# MohamedAazir_WirelessEMG__version_1_0_PC.net
KiCad netlist of a schematic drawn in Altium Designer
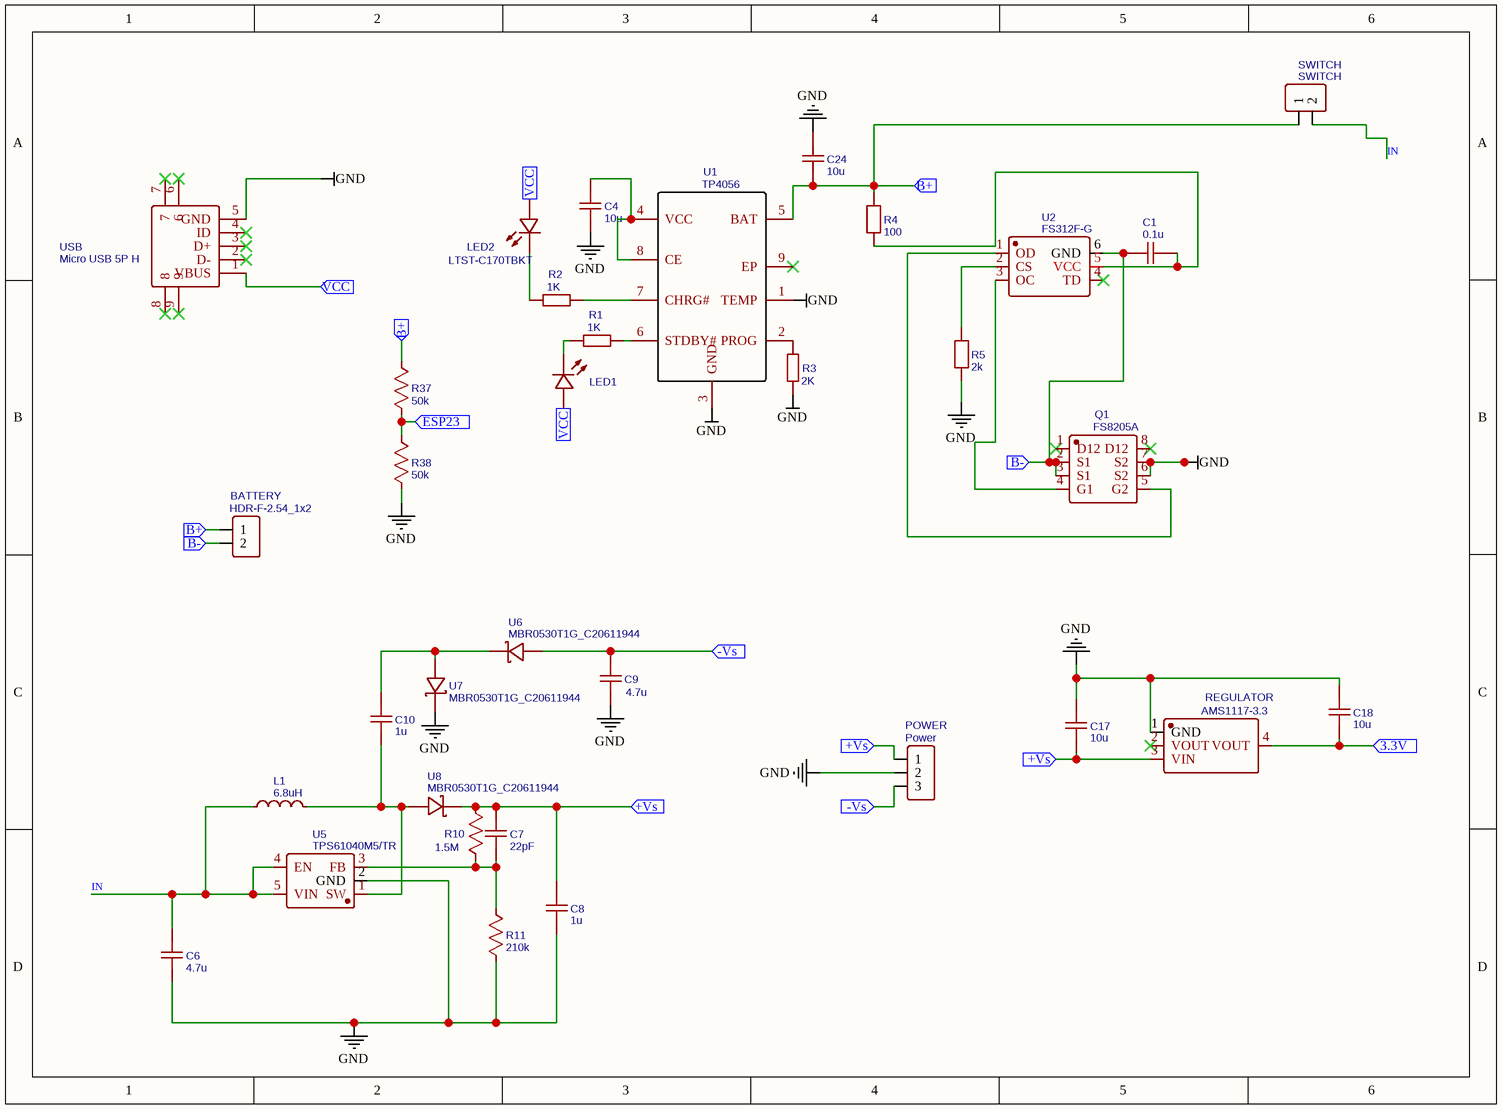
[diagram p0: MohamedAazir_WirelessEMG__version_1.0_PCB__Power.schdoc]

(export (version "E")
  (design (tool "Eeschema 10.0.6"))
  (components
    (comp (ref "BATTERY")
      (value "HDR-F-2.54_1x2")
      (fields
        (field (name "MANUFACTURER") "HC(虹成电子)")
        (field (name "MANUFACTURER PART") "HC-PM254-8.5H-1x2PZ")
        (field (name "CONTRIBUTOR") "LCEDA_Lib")
      )
      (libsource (lib "altium-import") (part "root_0_HDR-F-2.54_1x2_"))
    )
    (comp (ref "C1")
      (value "0.1u")
      (fields
        (field (name "MANUFACTURER PART") "RF18N0R1B500CT")
        (field (name "MANUFACTURER") "Walsin(华新科)")
        (field (name "CONTRIBUTOR") "LCEDA_Lib")
      )
      (libsource (lib "altium-import") (part "root_0_0.1u_"))
    )
    (comp (ref "C4")
      (value "10u")
      (fields
        (field (name "MANUFACTURER PART") "CA45A-P-10V-10uF-K")
        (field (name "MANUFACTURER") "CEC(振华新云)")
        (field (name "CONTRIBUTOR") "LCEDA_Lib")
      )
      (libsource (lib "altium-import") (part "root_3_10u_"))
    )
    (comp (ref "C6")
      (value "4.7u")
      (fields
        (field (name "MANUFACTURER PART") "CA45B-A-25V-4.7UF-K")
        (field (name "MANUFACTURER") "CEC(振华新云)")
        (field (name "CONTRIBUTOR") "LCEDA_Lib")
      )
      (libsource (lib "altium-import") (part "root_1_4.7u_"))
    )
    (comp (ref "C7")
      (value "22pF")
      (fields
        (field (name "MANUFACTURER PART") "0805N220J500CT-C")
        (field (name "MANUFACTURER") "Walsin(华新科)")
        (field (name "CONTRIBUTOR") "LCEDA_Lib")
      )
      (libsource (lib "altium-import") (part "root_1_22pF_"))
    )
    (comp (ref "C8")
      (value "1u")
      (fields
        (field (name "MANUFACTURER PART") "T491B105M035AT")
        (field (name "MANUFACTURER") "KEMET(基美)")
        (field (name "CONTRIBUTOR") "LCEDA_Lib")
      )
      (libsource (lib "altium-import") (part "root_1_1u_"))
    )
    (comp (ref "C9")
      (value "4.7u")
      (fields
        (field (name "MANUFACTURER PART") "CA45B-A-25V-4.7UF-K")
        (field (name "MANUFACTURER") "CEC(振华新云)")
        (field (name "CONTRIBUTOR") "LCEDA_Lib")
      )
      (libsource (lib "altium-import") (part "root_1_4.7u_"))
    )
    (comp (ref "C10")
      (value "1u")
      (fields
        (field (name "MANUFACTURER PART") "T491B105M035AT")
        (field (name "MANUFACTURER") "KEMET(基美)")
        (field (name "CONTRIBUTOR") "LCEDA_Lib")
      )
      (libsource (lib "altium-import") (part "root_1_1u_"))
    )
    (comp (ref "C17")
      (value "10u")
      (fields
        (field (name "MANUFACTURER PART") "CGA3E1X7T0G106MT0YHN")
        (field (name "MANUFACTURER") "TDK")
        (field (name "CONTRIBUTOR") "LCEDA_Lib")
      )
      (libsource (lib "altium-import") (part "root_1_10u_"))
    )
    (comp (ref "C18")
      (value "10u")
      (fields
        (field (name "MANUFACTURER PART") "CGA3E1X7T0G106MT0YHN")
        (field (name "MANUFACTURER") "TDK")
        (field (name "CONTRIBUTOR") "LCEDA_Lib")
      )
      (libsource (lib "altium-import") (part "root_1_10u_"))
    )
    (comp (ref "C24")
      (value "10u")
      (fields (field (name "CONTRIBUTOR") "LCEDA_Lib"))
      (libsource (lib "altium-import") (part "root_1_10u_"))
    )
    (comp (ref "L1")
      (value "6.8uH")
      (fields
        (field (name "MANUFACTURER PART") "BWVF00303015220M00")
        (field (name "MANUFACTURER") "chilisin(奇力新)")
        (field (name "CONTRIBUTOR") "LCEDA_Lib")
      )
      (libsource (lib "altium-import") (part "root_0_6.8uH_"))
    )
    (comp (ref "LED1")
      (value "0805G (Green)")
      (fields (field (name "MANUFACTURER") "KENTO"))
      (libsource (lib "altium-import") (part "root_3_0805G (Green)_"))
    )
    (comp (ref "LED2")
      (value "LTST-C170TBKT")
      (fields (field (name "MANUFACTURER PART") "LED05-红灯") (field (name "CONTRIBUTOR") "LCSC"))
      (libsource (lib "altium-import") (part "root_1_LTST-C170TBKT_"))
    )
    (comp (ref "POWER")
      (value "Power")
      (fields (field (name "MANUFACTURER") "BOOMELE(博穆精密)") (field (name "MANUFACTURER PART") "2.54-1*3P母"))
      (libsource (lib "altium-import") (part "root_0_Power_"))
    )
    (comp (ref "Q1")
      (value "FS8205A")
      (fields (field (name "MANUFACTURER") "FORTUNE"))
      (libsource (lib "altium-import") (part "root_0_FS8205A_"))
    )
    (comp (ref "R1")
      (value "1K")
      (fields
        (field (name "MANUFACTURER") "ResistorToday")
        (field (name "MANUFACTURER PART") "AECR0603F1K00K9")
        (field (name "CONTRIBUTOR") "LCSC")
      )
      (libsource (lib "altium-import") (part "root_0_1K_"))
    )
    (comp (ref "R2")
      (value "1K")
      (fields
        (field (name "MANUFACTURER") "ResistorToday")
        (field (name "MANUFACTURER PART") "AECR0603F1K00K9")
        (field (name "CONTRIBUTOR") "LCSC")
      )
      (libsource (lib "altium-import") (part "root_0_1K_"))
    )
    (comp (ref "R3")
      (value "2K")
      (fields
        (field (name "MANUFACTURER") "Tyohm")
        (field (name "MANUFACTURER PART") "RMC06031.2K5%N")
        (field (name "CONTRIBUTOR") "LCSC")
      )
      (libsource (lib "altium-import") (part "root_1_2K_"))
    )
    (comp (ref "R4")
      (value "100")
      (fields
        (field (name "MANUFACTURER PART") "RC0R5DB100RJET")
        (field (name "MANUFACTURER") "Ohmite")
        (field (name "CONTRIBUTOR") "LCEDA_Lib")
      )
      (libsource (lib "altium-import") (part "root_3_100_"))
    )
    (comp (ref "R5")
      (value "2k")
      (fields
        (field (name "MANUFACTURER PART") "CSR0204FTDV2001")
        (field (name "MANUFACTURER") "Viking(光颉)")
        (field (name "CONTRIBUTOR") "LCEDA_Lib")
      )
      (libsource (lib "altium-import") (part "root_1_2k_"))
    )
    (comp (ref "R10")
      (value "1.5M")
      (fields
        (field (name "MANUFACTURER PART") "WR02X155JAL")
        (field (name "MANUFACTURER") "Walsin(华新科)")
        (field (name "CONTRIBUTOR") "LCEDA_Lib")
      )
      (libsource (lib "altium-import") (part "root_1_1.5M_"))
    )
    (comp (ref "R11")
      (value "210k")
      (fields
        (field (name "MANUFACTURER PART") "FRC0805F2103TS")
        (field (name "MANUFACTURER") "FOJAN(富捷)")
        (field (name "CONTRIBUTOR") "LCEDA_Lib")
      )
      (libsource (lib "altium-import") (part "root_1_210k_"))
    )
    (comp (ref "R37")
      (value "50k")
      (fields
        (field (name "MANUFACTURER PART") "RT0603BRD0750KL")
        (field (name "MANUFACTURER") "YAGEO(国巨)")
        (field (name "CONTRIBUTOR") "LCEDA_Lib")
      )
      (libsource (lib "altium-import") (part "root_1_50k_"))
    )
    (comp (ref "R38")
      (value "50k")
      (fields
        (field (name "MANUFACTURER PART") "RT0603BRD0750KL")
        (field (name "MANUFACTURER") "YAGEO(国巨)")
        (field (name "CONTRIBUTOR") "LCEDA_Lib")
      )
      (libsource (lib "altium-import") (part "root_1_50k_"))
    )
    (comp (ref "REGULATOR")
      (value "AMS1117-3.3")
      (fields (field (name "MANUFACTURER") "AMS"))
      (libsource (lib "altium-import") (part "root_0_AMS1117-3.3_"))
    )
    (comp (ref "SWITCH")
      (value "SWITCH")
      (fields
        (field (name "MANUFACTURER") "HC(虹成电子)")
        (field (name "MANUFACTURER PART") "HC-PM254-8.5H-1x2PZ")
        (field (name "CONTRIBUTOR") "LCEDA_Lib")
      )
      (libsource (lib "altium-import") (part "root_1_SWITCH_"))
    )
    (comp (ref "U1")
      (value "TP4056")
      (fields (field (name "MANUFACTURER") "TOPPOWER") (field (name "CONTRIBUTOR") "Guest"))
      (libsource (lib "altium-import") (part "root_0_TP4056_"))
    )
    (comp (ref "U2")
      (value "FS312F-G")
      (fields (field (name "MANUFACTURER") "FORTUNE(富晶)"))
      (libsource (lib "altium-import") (part "root_0_FS312F-G_"))
    )
    (comp (ref "U5")
      (value "TPS61040M5/TR")
      (fields (field (name "MANUFACTURER") "HGSEMI(华冠)") (field (name "CONTRIBUTOR") "lcsc"))
      (libsource (lib "altium-import") (part "root_2_TPS61040M5/TR_"))
    )
    (comp (ref "U6")
      (value "MBR0530T1G_C20611944")
      (fields
        (field (name "MANUFACTURER") "HXY MOSFET(华轩阳电子)")
        (field (name "MANUFACTURER PART") "MBR0530T1G")
        (field (name "CONTRIBUTOR") "lcsc")
      )
      (libsource (lib "altium-import") (part "root_0_MBR0530T1G_C20611944_"))
    )
    (comp (ref "U7")
      (value "MBR0530T1G_C20611944")
      (fields
        (field (name "MANUFACTURER") "HXY MOSFET(华轩阳电子)")
        (field (name "MANUFACTURER PART") "MBR0530T1G")
        (field (name "CONTRIBUTOR") "lcsc")
      )
      (libsource (lib "altium-import") (part "root_1_MBR0530T1G_C20611944_"))
    )
    (comp (ref "U8")
      (value "MBR0530T1G_C20611944")
      (fields
        (field (name "MANUFACTURER") "HXY MOSFET(华轩阳电子)")
        (field (name "MANUFACTURER PART") "MBR0530T1G")
        (field (name "CONTRIBUTOR") "lcsc")
      )
      (libsource (lib "altium-import") (part "root_2_MBR0530T1G_C20611944_"))
    )
    (comp (ref "USB")
      (value "Micro USB 5P H")
      (fields
        (field (name "MANUFACTURER") "精拓金")
        (field (name "MANUFACTURER PART") "920-E52A2021S10101")
        (field (name "CONTRIBUTOR") "LCSC")
      )
      (libsource (lib "altium-import") (part "root_2_Micro USB 5P H_"))
    )
  )
  (nets
    (net (code "1") (name "/+Vs") (class "Default")
      (node (ref "C17") (pin "1") (pinfunction "1_1") (pintype "passive"))
      (node (ref "C7") (pin "2") (pinfunction "2_2") (pintype "passive"))
      (node (ref "C8") (pin "2") (pinfunction "2_2") (pintype "passive"))
      (node (ref "POWER") (pin "1") (pinfunction "1_1") (pintype "passive"))
      (node (ref "R10") (pin "2") (pinfunction "2_2") (pintype "passive"))
      (node (ref "REGULATOR") (pin "3") (pinfunction "VIN_3") (pintype "passive"))
      (node (ref "U8") (pin "1") (pinfunction "K_1") (pintype "passive"))
    )
    (net (code "2") (name "/-Vs") (class "Default")
      (node (ref "C9") (pin "2") (pinfunction "2_2") (pintype "passive"))
      (node (ref "POWER") (pin "3") (pinfunction "3_3") (pintype "passive"))
      (node (ref "U6") (pin "2") (pinfunction "A_2") (pintype "passive"))
    )
    (net (code "3") (name "/3.3V") (class "Default")
      (node (ref "C18") (pin "1") (pinfunction "1_1") (pintype "passive"))
      (node (ref "REGULATOR") (pin "4") (pinfunction "VOUT_4") (pintype "passive"))
    )
    (net (code "4") (name "/B+") (class "Default")
      (node (ref "BATTERY") (pin "1") (pinfunction "1_1") (pintype "passive"))
      (node (ref "C24") (pin "1") (pinfunction "1_1") (pintype "passive"))
      (node (ref "R37") (pin "2") (pinfunction "2_2") (pintype "passive"))
      (node (ref "R4") (pin "1") (pinfunction "1_1") (pintype "passive"))
      (node (ref "SWITCH") (pin "1") (pinfunction "1_1") (pintype "passive"))
      (node (ref "U1") (pin "5") (pinfunction "BAT_5") (pintype "passive"))
    )
    (net (code "5") (name "/B-") (class "Default")
      (node (ref "BATTERY") (pin "2") (pinfunction "2_2") (pintype "passive"))
      (node (ref "C1") (pin "1") (pinfunction "1_1") (pintype "passive"))
      (node (ref "Q1") (pin "2") (pinfunction "S1_2") (pintype "passive"))
      (node (ref "Q1") (pin "3") (pinfunction "S1_3") (pintype "passive"))
      (node (ref "U2") (pin "6") (pinfunction "GND_6") (pintype "passive"))
    )
    (net (code "6") (name "/ESP23") (class "Default")
      (node (ref "R37") (pin "1") (pinfunction "1_1") (pintype "passive"))
      (node (ref "R38") (pin "2") (pinfunction "2_2") (pintype "passive"))
    )
    (net (code "7") (name "/IN") (class "Default")
      (node (ref "C6") (pin "2") (pinfunction "2_2") (pintype "passive"))
      (node (ref "L1") (pin "1") (pinfunction "1_1") (pintype "passive"))
      (node (ref "SWITCH") (pin "2") (pinfunction "2_2") (pintype "passive"))
      (node (ref "U5") (pin "4") (pinfunction "EN_4") (pintype "passive"))
      (node (ref "U5") (pin "5") (pinfunction "VIN_5") (pintype "passive"))
    )
    (net (code "8") (name "/VCC") (class "Default")
      (node (ref "LED1") (pin "2") (pinfunction "A_2") (pintype "passive"))
      (node (ref "LED2") (pin "2") (pinfunction "A_2") (pintype "passive"))
      (node (ref "USB") (pin "1") (pinfunction "VBUS_1") (pintype "passive"))
    )
    (net (code "9") (name "GND") (class "Default")
      (node (ref "C17") (pin "2") (pinfunction "2_2") (pintype "passive"))
      (node (ref "C18") (pin "2") (pinfunction "2_2") (pintype "passive"))
      (node (ref "C24") (pin "2") (pinfunction "2_2") (pintype "passive"))
      (node (ref "C4") (pin "2") (pinfunction "2_2") (pintype "passive"))
      (node (ref "C6") (pin "1") (pinfunction "1_1") (pintype "passive"))
      (node (ref "C8") (pin "1") (pinfunction "1_1") (pintype "passive"))
      (node (ref "C9") (pin "1") (pinfunction "1_1") (pintype "passive"))
      (node (ref "POWER") (pin "2") (pinfunction "2_2") (pintype "passive"))
      (node (ref "Q1") (pin "6") (pinfunction "S2_6") (pintype "passive"))
      (node (ref "Q1") (pin "7") (pinfunction "S2_7") (pintype "passive"))
      (node (ref "R11") (pin "1") (pinfunction "1_1") (pintype "passive"))
      (node (ref "R3") (pin "1") (pinfunction "1_1") (pintype "passive"))
      (node (ref "R38") (pin "1") (pinfunction "1_1") (pintype "passive"))
      (node (ref "R5") (pin "1") (pinfunction "1_1") (pintype "passive"))
      (node (ref "REGULATOR") (pin "1") (pinfunction "GND_1") (pintype "passive"))
      (node (ref "U1") (pin "1") (pinfunction "TEMP_1") (pintype "passive"))
      (node (ref "U1") (pin "3") (pinfunction "GND_3") (pintype "passive"))
      (node (ref "U5") (pin "2") (pinfunction "GND_2") (pintype "passive"))
      (node (ref "U7") (pin "1") (pinfunction "K_1") (pintype "passive"))
      (node (ref "USB") (pin "5") (pinfunction "GND_5") (pintype "passive"))
    )
    (net (code "10") (name "Net-(LED1-K)") (class "Default")
      (node (ref "LED1") (pin "1") (pinfunction "K_1") (pintype "passive"))
      (node (ref "R1") (pin "1") (pinfunction "1_1") (pintype "passive"))
    )
    (net (code "11") (name "Net-(LED2-K)") (class "Default")
      (node (ref "LED2") (pin "1") (pinfunction "K_1") (pintype "passive"))
      (node (ref "R2") (pin "1") (pinfunction "1_1") (pintype "passive"))
    )
    (net (code "12") (name "Net-(Q1-G1)") (class "Default")
      (node (ref "Q1") (pin "4") (pinfunction "G1_4") (pintype "passive"))
      (node (ref "U2") (pin "3") (pinfunction "OC_3") (pintype "passive"))
    )
    (net (code "13") (name "Net-(Q1-G2)") (class "Default")
      (node (ref "Q1") (pin "5") (pinfunction "G2_5") (pintype "passive"))
      (node (ref "U2") (pin "1") (pinfunction "OD_1") (pintype "passive"))
    )
    (net (code "14") (name "Net-(U1-CE)") (class "Default")
      (node (ref "C4") (pin "1") (pinfunction "1_1") (pintype "passive"))
      (node (ref "U1") (pin "4") (pinfunction "VCC_4") (pintype "passive"))
      (node (ref "U1") (pin "8") (pinfunction "CE_8") (pintype "passive"))
    )
    (net (code "15") (name "Net-(U1-CHRG#)") (class "Default")
      (node (ref "R2") (pin "2") (pinfunction "2_2") (pintype "passive"))
      (node (ref "U1") (pin "7") (pinfunction "CHRG#_7") (pintype "passive"))
    )
    (net (code "16") (name "Net-(U1-PROG)") (class "Default")
      (node (ref "R3") (pin "2") (pinfunction "2_2") (pintype "passive"))
      (node (ref "U1") (pin "2") (pinfunction "PROG_2") (pintype "passive"))
    )
    (net (code "17") (name "Net-(U1-STDBY#)") (class "Default")
      (node (ref "R1") (pin "2") (pinfunction "2_2") (pintype "passive"))
      (node (ref "U1") (pin "6") (pinfunction "STDBY#_6") (pintype "passive"))
    )
    (net (code "18") (name "Net-(U2-CS)") (class "Default")
      (node (ref "R5") (pin "2") (pinfunction "2_2") (pintype "passive"))
      (node (ref "U2") (pin "2") (pinfunction "CS_2") (pintype "passive"))
    )
    (net (code "19") (name "Net-(U2-VCC)") (class "Default")
      (node (ref "C1") (pin "2") (pinfunction "2_2") (pintype "passive"))
      (node (ref "R4") (pin "2") (pinfunction "2_2") (pintype "passive"))
      (node (ref "U2") (pin "5") (pinfunction "VCC_5") (pintype "passive"))
    )
    (net (code "20") (name "Net-(U5-FB)") (class "Default")
      (node (ref "C7") (pin "1") (pinfunction "1_1") (pintype "passive"))
      (node (ref "R10") (pin "1") (pinfunction "1_1") (pintype "passive"))
      (node (ref "R11") (pin "2") (pinfunction "2_2") (pintype "passive"))
      (node (ref "U5") (pin "3") (pinfunction "FB_3") (pintype "passive"))
    )
    (net (code "21") (name "Net-(U5-SW)") (class "Default")
      (node (ref "C10") (pin "1") (pinfunction "1_1") (pintype "passive"))
      (node (ref "L1") (pin "2") (pinfunction "2_2") (pintype "passive"))
      (node (ref "U5") (pin "1") (pinfunction "SW_1") (pintype "passive"))
      (node (ref "U8") (pin "2") (pinfunction "A_2") (pintype "passive"))
    )
    (net (code "22") (name "Net-(U6-K)") (class "Default")
      (node (ref "C10") (pin "2") (pinfunction "2_2") (pintype "passive"))
      (node (ref "U6") (pin "1") (pinfunction "K_1") (pintype "passive"))
      (node (ref "U7") (pin "2") (pinfunction "A_2") (pintype "passive"))
    )
    (net (code "23") (name "unconnected-(Q1-D12-Pad1)") (class "Default")
      (node (ref "Q1") (pin "1") (pinfunction "D12_1") (pintype "passive+no_connect"))
    )
    (net (code "24") (name "unconnected-(Q1-D12-Pad8)") (class "Default")
      (node (ref "Q1") (pin "8") (pinfunction "D12_8") (pintype "passive+no_connect"))
    )
    (net (code "25") (name "unconnected-(REGULATOR-VOUT-Pad2)") (class "Default")
      (node (ref "REGULATOR") (pin "2") (pinfunction "VOUT_2") (pintype "passive+no_connect"))
    )
    (net (code "26") (name "unconnected-(U1-EP-Pad9)") (class "Default")
      (node (ref "U1") (pin "9") (pinfunction "EP_9") (pintype "passive+no_connect"))
    )
    (net (code "27") (name "unconnected-(U2-TD-Pad4)") (class "Default")
      (node (ref "U2") (pin "4") (pinfunction "TD_4") (pintype "passive+no_connect"))
    )
    (net (code "28") (name "unconnected-(USB-D+-Pad3)") (class "Default")
      (node (ref "USB") (pin "3") (pinfunction "D+_3") (pintype "passive+no_connect"))
    )
    (net (code "29") (name "unconnected-(USB-D--Pad2)") (class "Default")
      (node (ref "USB") (pin "2") (pinfunction "D-_2") (pintype "passive+no_connect"))
    )
    (net (code "30") (name "unconnected-(USB-ID-Pad4)") (class "Default")
      (node (ref "USB") (pin "4") (pinfunction "ID_4") (pintype "passive+no_connect"))
    )
    (net (code "31") (name "unconnected-(USB-Pad6)") (class "Default")
      (node (ref "USB") (pin "6") (pinfunction "6_6") (pintype "passive+no_connect"))
    )
    (net (code "32") (name "unconnected-(USB-Pad7)") (class "Default")
      (node (ref "USB") (pin "7") (pinfunction "7_7") (pintype "passive+no_connect"))
    )
    (net (code "33") (name "unconnected-(USB-Pad8)") (class "Default")
      (node (ref "USB") (pin "8") (pinfunction "8_8") (pintype "passive+no_connect"))
    )
    (net (code "34") (name "unconnected-(USB-Pad9)") (class "Default")
      (node (ref "USB") (pin "9") (pinfunction "9_9") (pintype "passive+no_connect"))
    )
  )
)
